# TIDA-00643_8305.net
KiCad netlist of a schematic drawn in Altium Designer
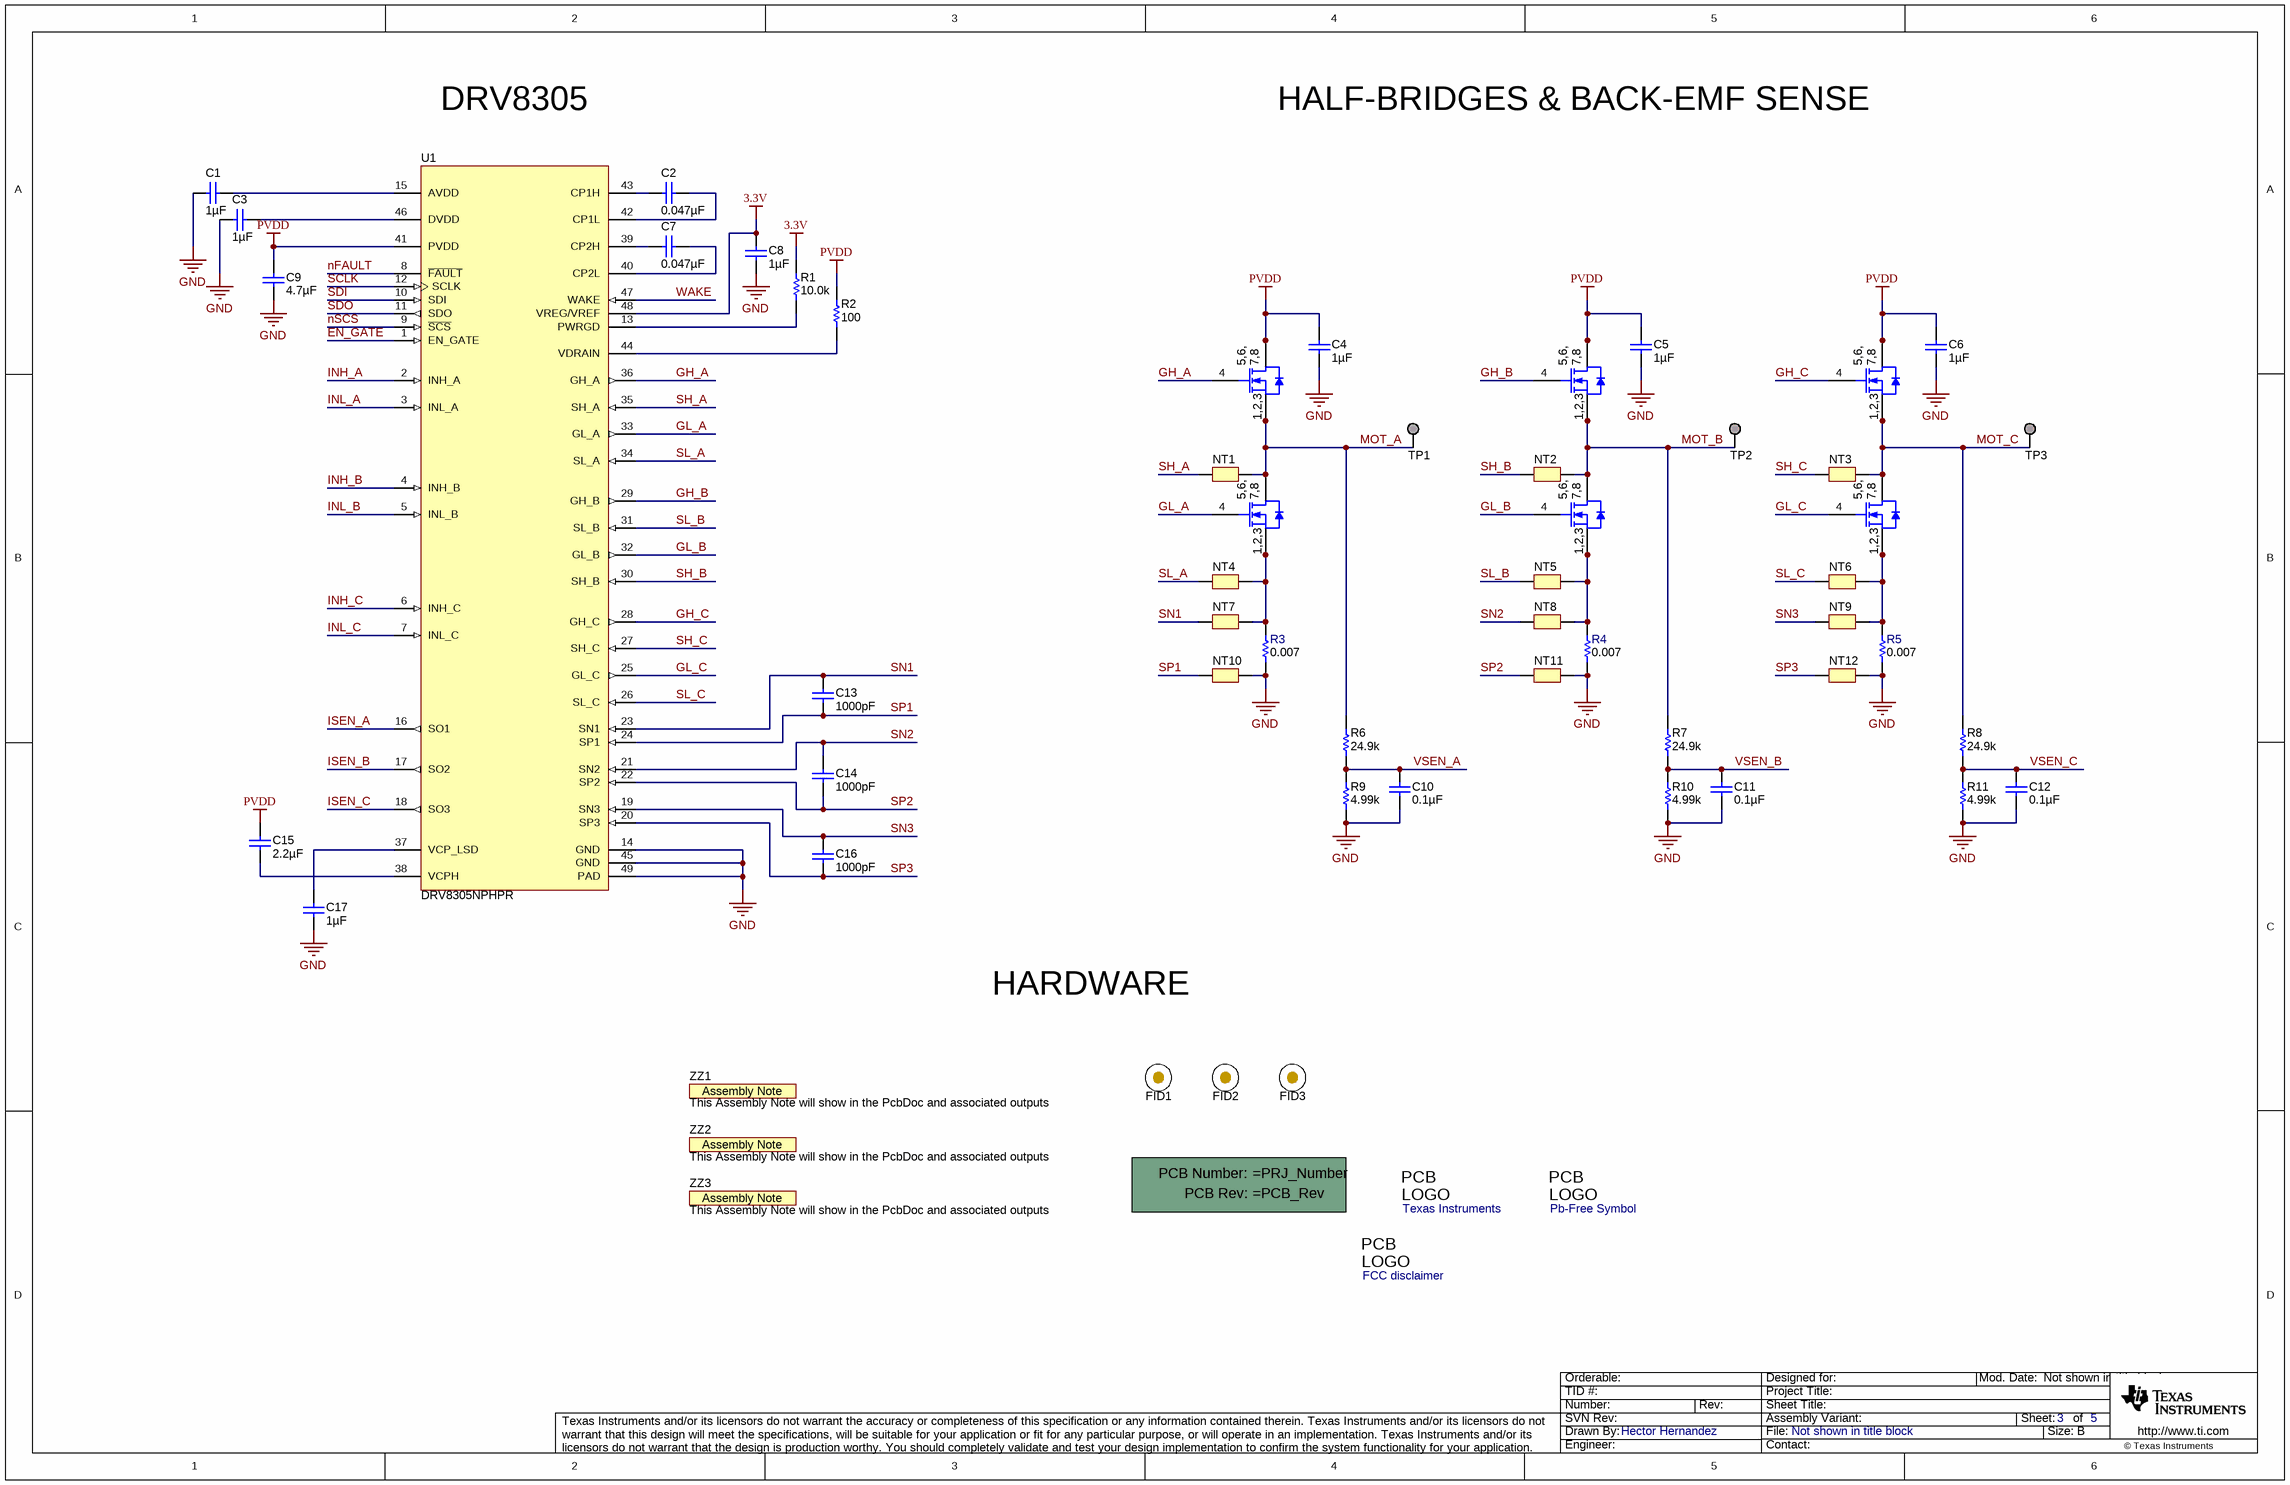
[diagram p0: TIDA-00643_8305.SchDoc]

(export (version "E")
  (design (tool "Eeschema 10.0.6"))
  (components
    (comp (ref "!PCB1")
      (value "Printed Circuit Board")
      (fields
        (field (name "MANUFACTURER") "Any")
        (field (name "SYMBOLCREATOR") "a0412235")
        (field (name "PUBLISHER") "Texas Instruments")
      )
      (libsource (lib "Hardware") (part "PCB"))
    )
    (comp (ref "C1")
      (value "GMK107BJ105KA-T")
      (footprint "0603L")
      (description "CAP, CERM, 1 µF, 35 V, +/- 10%, X5R, 0603")
      (fields
        (field (name "VALUEDISPLAYED") "1µF")
        (field (name "MANUFACTURER") "Taiyo Yuden")
        (field (name "PUBLISHER") "Texas Instruments")
      )
      (libsource (lib "Capacitor_Ceramic") (part "GMK107BJ105KA-T"))
    )
    (comp (ref "C2")
      (value "GRM188R71E473KA01D")
      (footprint "0603L")
      (description "CAP, CERM, 0.047 µF, 25 V, +/- 10%, X7R, 0603")
      (fields
        (field (name "VALUEDISPLAYED") "0.047µF")
        (field (name "MANUFACTURER") "MuRata")
        (field (name "PUBLISHER") "Texas Instruments")
      )
      (libsource (lib "Capacitor_Ceramic") (part "GRM188R71E473KA01D"))
    )
    (comp (ref "C3")
      (value "GMK107BJ105KA-T")
      (footprint "0603L")
      (description "CAP, CERM, 1 µF, 35 V, +/- 10%, X5R, 0603")
      (fields
        (field (name "VALUEDISPLAYED") "1µF")
        (field (name "MANUFACTURER") "Taiyo Yuden")
        (field (name "PUBLISHER") "Texas Instruments")
      )
      (libsource (lib "Capacitor_Ceramic") (part "GMK107BJ105KA-T"))
    )
    (comp (ref "C4")
      (value "GMK107BJ105KA-T")
      (footprint "0603L")
      (description "CAP, CERM, 1 µF, 35 V, +/- 10%, X5R, 0603")
      (fields
        (field (name "VALUEDISPLAYED") "1µF")
        (field (name "MANUFACTURER") "Taiyo Yuden")
        (field (name "PUBLISHER") "Texas Instruments")
      )
      (libsource (lib "Capacitor_Ceramic") (part "GMK107BJ105KA-T"))
    )
    (comp (ref "C5")
      (value "GMK107BJ105KA-T")
      (footprint "0603L")
      (description "CAP, CERM, 1 µF, 35 V, +/- 10%, X5R, 0603")
      (fields
        (field (name "VALUEDISPLAYED") "1µF")
        (field (name "MANUFACTURER") "Taiyo Yuden")
        (field (name "PUBLISHER") "Texas Instruments")
      )
      (libsource (lib "Capacitor_Ceramic") (part "GMK107BJ105KA-T"))
    )
    (comp (ref "C6")
      (value "GMK107BJ105KA-T")
      (footprint "0603L")
      (description "CAP, CERM, 1 µF, 35 V, +/- 10%, X5R, 0603")
      (fields
        (field (name "VALUEDISPLAYED") "1µF")
        (field (name "MANUFACTURER") "Taiyo Yuden")
        (field (name "PUBLISHER") "Texas Instruments")
      )
      (libsource (lib "Capacitor_Ceramic") (part "GMK107BJ105KA-T"))
    )
    (comp (ref "C7")
      (value "GRM188R71E473KA01D")
      (footprint "0603L")
      (description "CAP, CERM, 0.047 µF, 25 V, +/- 10%, X7R, 0603")
      (fields
        (field (name "VALUEDISPLAYED") "0.047µF")
        (field (name "MANUFACTURER") "MuRata")
        (field (name "PUBLISHER") "Texas Instruments")
      )
      (libsource (lib "Capacitor_Ceramic") (part "GRM188R71E473KA01D"))
    )
    (comp (ref "C8")
      (value "GRM188R61C105KA93D")
      (footprint "0603L")
      (description "CAP, CERM, 1 µF, 16 V, +/- 10%, X5R, 0603")
      (fields
        (field (name "VALUEDISPLAYED") "1µF")
        (field (name "MANUFACTURER") "MuRata")
        (field (name "PUBLISHER") "Texas Instruments")
      )
      (libsource (lib "Capacitor_Ceramic") (part "GRM188R61C105KA93D"))
    )
    (comp (ref "C9")
      (value "GRM188R6YA475KE15D")
      (footprint "0603_100L")
      (description "CAP, CERM, 4.7 µF, 35 V, +/- 10%, X5R, 0603")
      (fields
        (field (name "VALUEDISPLAYED") "4.7µF")
        (field (name "MANUFACTURER") "MuRata")
        (field (name "PUBLISHER") "Texas Instruments")
      )
      (libsource (lib "Capacitor_Ceramic") (part "GRM188R6YA475KE15D"))
    )
    (comp (ref "C10")
      (value "885012105016")
      (footprint "0402L")
      (description "CAP, CERM, 0.1 µF, 16 V, +/- 20%, X5R, 0402")
      (fields
        (field (name "VALUEDISPLAYED") "0.1µF")
        (field (name "MANUFACTURER") "Wurth Elektronik")
        (field (name "PUBLISHER") "Texas Instruments")
      )
      (libsource (lib "Capacitor_Ceramic") (part "885012105016"))
    )
    (comp (ref "C11")
      (value "885012105016")
      (footprint "0402L")
      (description "CAP, CERM, 0.1 µF, 16 V, +/- 20%, X5R, 0402")
      (fields
        (field (name "VALUEDISPLAYED") "0.1µF")
        (field (name "MANUFACTURER") "Wurth Elektronik")
        (field (name "PUBLISHER") "Texas Instruments")
      )
      (libsource (lib "Capacitor_Ceramic") (part "885012105016"))
    )
    (comp (ref "C12")
      (value "885012105016")
      (footprint "0402L")
      (description "CAP, CERM, 0.1 µF, 16 V, +/- 20%, X5R, 0402")
      (fields
        (field (name "VALUEDISPLAYED") "0.1µF")
        (field (name "MANUFACTURER") "Wurth Elektronik")
        (field (name "PUBLISHER") "Texas Instruments")
      )
      (libsource (lib "Capacitor_Ceramic") (part "885012105016"))
    )
    (comp (ref "C13")
      (value "GRM1555C1H102JA01D")
      (footprint "0402L")
      (description "CAP, CERM, 1000 pF, 50 V, +/- 5%, C0G/NP0, 0402")
      (fields
        (field (name "VALUEDISPLAYED") "1000pF")
        (field (name "MANUFACTURER") "MuRata")
        (field (name "PUBLISHER") "Texas Instruments")
      )
      (libsource (lib "Capacitor_Ceramic") (part "GRM1555C1H102JA01D"))
    )
    (comp (ref "C14")
      (value "GRM1555C1H102JA01D")
      (footprint "0402L")
      (description "CAP, CERM, 1000 pF, 50 V, +/- 5%, C0G/NP0, 0402")
      (fields
        (field (name "VALUEDISPLAYED") "1000pF")
        (field (name "MANUFACTURER") "MuRata")
        (field (name "PUBLISHER") "Texas Instruments")
      )
      (libsource (lib "Capacitor_Ceramic") (part "GRM1555C1H102JA01D"))
    )
    (comp (ref "C15")
      (value "GRM188R6YA225KA12D")
      (footprint "0603L")
      (description "CAP, CERM, 2.2 µF, 35 V, +/- 10%, X5R, 0603")
      (fields
        (field (name "VALUEDISPLAYED") "2.2µF")
        (field (name "MANUFACTURER") "MuRata")
        (field (name "PUBLISHER") "Texas Instruments")
      )
      (libsource (lib "Capacitor_Ceramic") (part "GRM188R6YA225KA12D"))
    )
    (comp (ref "C16")
      (value "GRM1555C1H102JA01D")
      (footprint "0402L")
      (description "CAP, CERM, 1000 pF, 50 V, +/- 5%, C0G/NP0, 0402")
      (fields
        (field (name "VALUEDISPLAYED") "1000pF")
        (field (name "MANUFACTURER") "MuRata")
        (field (name "PUBLISHER") "Texas Instruments")
      )
      (libsource (lib "Capacitor_Ceramic") (part "GRM1555C1H102JA01D"))
    )
    (comp (ref "C17")
      (value "GMK107BJ105KA-T")
      (footprint "0603L")
      (description "CAP, CERM, 1 µF, 35 V, +/- 10%, X5R, 0603")
      (fields
        (field (name "VALUEDISPLAYED") "1µF")
        (field (name "MANUFACTURER") "Taiyo Yuden")
        (field (name "PUBLISHER") "Texas Instruments")
      )
      (libsource (lib "Capacitor_Ceramic") (part "GMK107BJ105KA-T"))
    )
    (comp (ref "FID1")
      (value "Fiducial")
      (footprint "Fiducial6.4-20")
      (description "Fiducial mark.  There is nothing to buy or mount.")
      (fields (field (name "SYMBOLCREATOR") "codlsc") (field (name "PUBLISHER") "Texas Instruments"))
      (libsource (lib "MiscParts") (part "Fiducial"))
    )
    (comp (ref "FID2")
      (value "Fiducial")
      (footprint "Fiducial6.4-20")
      (description "Fiducial mark.  There is nothing to buy or mount.")
      (fields (field (name "SYMBOLCREATOR") "codlsc") (field (name "PUBLISHER") "Texas Instruments"))
      (libsource (lib "MiscParts") (part "Fiducial"))
    )
    (comp (ref "FID3")
      (value "Fiducial")
      (footprint "Fiducial6.4-20")
      (description "Fiducial mark.  There is nothing to buy or mount.")
      (fields (field (name "SYMBOLCREATOR") "codlsc") (field (name "PUBLISHER") "Texas Instruments"))
      (libsource (lib "MiscParts") (part "Fiducial"))
    )
    (comp (ref "Logo1")
      (value "Texas Instruments")
      (footprint "TI_Symbol_Overlay_Small")
      (description "Texas Instrument Corporate Signature")
      (fields (field (name "SYMBOLCREATOR") "a0412235") (field (name "PUBLISHER") "Texas Instruments"))
      (libsource (lib "Logos") (part "TI_Logo"))
    )
    (comp (ref "Logo2")
      (value "Pb-Free Symbol")
      (footprint "Pb-Free_Overlay_Small")
      (fields (field (name "SYMBOLCREATOR") "a0412235") (field (name "PUBLISHER") "Texas Instruments"))
      (libsource (lib "Logos") (part "Pb-Free"))
    )
    (comp (ref "Logo3")
      (value "FCC disclaimer")
      (footprint "FCC_disclaimer_stacked")
      (description "FCC_disclaimer")
      (fields (field (name "SYMBOLCREATOR") "codlsc") (field (name "PUBLISHER") "Texas Instruments"))
      (libsource (lib "Logos") (part "FCC_disclaimer"))
    )
    (comp (ref "NT1")
      (value "Net-Tie")
      (footprint "Net-Tie_10mil")
      (description "Single point connection between nets.")
      (fields (field (name "SYMBOLCREATOR") "codlsc") (field (name "PUBLISHER") "Texas Instruments"))
      (libsource (lib "MiscParts") (part "Net-Tie"))
    )
    (comp (ref "NT2")
      (value "Net-Tie")
      (footprint "Net-Tie_10mil")
      (description "Single point connection between nets.")
      (fields (field (name "SYMBOLCREATOR") "codlsc") (field (name "PUBLISHER") "Texas Instruments"))
      (libsource (lib "MiscParts") (part "Net-Tie"))
    )
    (comp (ref "NT3")
      (value "Net-Tie")
      (footprint "Net-Tie_10mil")
      (description "Single point connection between nets.")
      (fields (field (name "SYMBOLCREATOR") "codlsc") (field (name "PUBLISHER") "Texas Instruments"))
      (libsource (lib "MiscParts") (part "Net-Tie"))
    )
    (comp (ref "NT4")
      (value "Net-Tie")
      (footprint "Net-Tie_10mil")
      (description "Single point connection between nets.")
      (fields (field (name "SYMBOLCREATOR") "codlsc") (field (name "PUBLISHER") "Texas Instruments"))
      (libsource (lib "MiscParts") (part "Net-Tie"))
    )
    (comp (ref "NT5")
      (value "Net-Tie")
      (footprint "Net-Tie_10mil")
      (description "Single point connection between nets.")
      (fields (field (name "SYMBOLCREATOR") "codlsc") (field (name "PUBLISHER") "Texas Instruments"))
      (libsource (lib "MiscParts") (part "Net-Tie"))
    )
    (comp (ref "NT6")
      (value "Net-Tie")
      (footprint "Net-Tie_10mil")
      (description "Single point connection between nets.")
      (fields (field (name "SYMBOLCREATOR") "codlsc") (field (name "PUBLISHER") "Texas Instruments"))
      (libsource (lib "MiscParts") (part "Net-Tie"))
    )
    (comp (ref "NT7")
      (value "Net-Tie")
      (footprint "Net-Tie_10mil")
      (description "Single point connection between nets.")
      (fields (field (name "SYMBOLCREATOR") "codlsc") (field (name "PUBLISHER") "Texas Instruments"))
      (libsource (lib "MiscParts") (part "Net-Tie"))
    )
    (comp (ref "NT8")
      (value "Net-Tie")
      (footprint "Net-Tie_10mil")
      (description "Single point connection between nets.")
      (fields (field (name "SYMBOLCREATOR") "codlsc") (field (name "PUBLISHER") "Texas Instruments"))
      (libsource (lib "MiscParts") (part "Net-Tie"))
    )
    (comp (ref "NT9")
      (value "Net-Tie")
      (footprint "Net-Tie_10mil")
      (description "Single point connection between nets.")
      (fields (field (name "SYMBOLCREATOR") "codlsc") (field (name "PUBLISHER") "Texas Instruments"))
      (libsource (lib "MiscParts") (part "Net-Tie"))
    )
    (comp (ref "NT10")
      (value "Net-Tie")
      (footprint "Net-Tie_10mil")
      (description "Single point connection between nets.")
      (fields (field (name "SYMBOLCREATOR") "codlsc") (field (name "PUBLISHER") "Texas Instruments"))
      (libsource (lib "MiscParts") (part "Net-Tie"))
    )
    (comp (ref "NT11")
      (value "Net-Tie")
      (footprint "Net-Tie_10mil")
      (description "Single point connection between nets.")
      (fields (field (name "SYMBOLCREATOR") "codlsc") (field (name "PUBLISHER") "Texas Instruments"))
      (libsource (lib "MiscParts") (part "Net-Tie"))
    )
    (comp (ref "NT12")
      (value "Net-Tie")
      (footprint "Net-Tie_10mil")
      (description "Single point connection between nets.")
      (fields (field (name "SYMBOLCREATOR") "codlsc") (field (name "PUBLISHER") "Texas Instruments"))
      (libsource (lib "MiscParts") (part "Net-Tie"))
    )
    (comp (ref "Q1")
      (value "CSD17573Q5B")
      (footprint "TRANS_NexFET_Q5B")
      (description "MOSFET, N-CH, 30 V, 100 A, SON 5x6mm")
      (fields
        (field (name "MANUFACTURER") "Texas Instruments")
        (field (name "PUBLISHER") "Texas Instruments")
      )
      (libsource (lib "FETs") (part "CSD17573Q5B"))
    )
    (comp (ref "Q2")
      (value "CSD17573Q5B")
      (footprint "TRANS_NexFET_Q5B")
      (description "MOSFET, N-CH, 30 V, 100 A, SON 5x6mm")
      (fields
        (field (name "MANUFACTURER") "Texas Instruments")
        (field (name "PUBLISHER") "Texas Instruments")
      )
      (libsource (lib "FETs") (part "CSD17573Q5B"))
    )
    (comp (ref "Q3")
      (value "CSD17573Q5B")
      (footprint "TRANS_NexFET_Q5B")
      (description "MOSFET, N-CH, 30 V, 100 A, SON 5x6mm")
      (fields
        (field (name "MANUFACTURER") "Texas Instruments")
        (field (name "PUBLISHER") "Texas Instruments")
      )
      (libsource (lib "FETs") (part "CSD17573Q5B"))
    )
    (comp (ref "Q4")
      (value "CSD17573Q5B")
      (footprint "TRANS_NexFET_Q5B")
      (description "MOSFET, N-CH, 30 V, 100 A, SON 5x6mm")
      (fields
        (field (name "MANUFACTURER") "Texas Instruments")
        (field (name "PUBLISHER") "Texas Instruments")
      )
      (libsource (lib "FETs") (part "CSD17573Q5B"))
    )
    (comp (ref "Q5")
      (value "CSD17573Q5B")
      (footprint "TRANS_NexFET_Q5B")
      (description "MOSFET, N-CH, 30 V, 100 A, SON 5x6mm")
      (fields
        (field (name "MANUFACTURER") "Texas Instruments")
        (field (name "PUBLISHER") "Texas Instruments")
      )
      (libsource (lib "FETs") (part "CSD17573Q5B"))
    )
    (comp (ref "Q6")
      (value "CSD17573Q5B")
      (footprint "TRANS_NexFET_Q5B")
      (description "MOSFET, N-CH, 30 V, 100 A, SON 5x6mm")
      (fields
        (field (name "MANUFACTURER") "Texas Instruments")
        (field (name "PUBLISHER") "Texas Instruments")
      )
      (libsource (lib "FETs") (part "CSD17573Q5B"))
    )
    (comp (ref "R1")
      (value "RC0603FR-0710KL")
      (footprint "0603L")
      (description "RES, 10.0 k, 1%, 0.1 W, 0603")
      (fields
        (field (name "VALUEDISPLAYED") "10.0k")
        (field (name "MANUFACTURER") "Yageo America")
        (field (name "PUBLISHER") "Texas Instruments")
      )
      (libsource (lib "Resistor_0603") (part "RC0603FR-0710KL"))
    )
    (comp (ref "R2")
      (value "RC0603FR-07100RL")
      (footprint "0603L")
      (description "RES, 100, 1%, 0.1 W, 0603")
      (fields
        (field (name "VALUEDISPLAYED") "100")
        (field (name "MANUFACTURER") "Yageo America")
        (field (name "PUBLISHER") "Texas Instruments")
      )
      (libsource (lib "Resistor_0603") (part "RC0603FR-07100RL"))
    )
    (comp (ref "R3")
      (value "PMR100HZPFU7L00")
      (footprint "2512L")
      (description "RES, 0.007, 1%, 2 W, 2512")
      (fields
        (field (name "VALUEDISPLAYED") "0.007")
        (field (name "MANUFACTURER") "Rohm")
        (field (name "PUBLISHER") "Texas Instruments")
      )
      (libsource (lib "Resistor_2512") (part "PMR100HZPFU7L00"))
    )
    (comp (ref "R4")
      (value "PMR100HZPFU7L00")
      (footprint "2512L")
      (description "RES, 0.007, 1%, 2 W, 2512")
      (fields
        (field (name "VALUEDISPLAYED") "0.007")
        (field (name "MANUFACTURER") "Rohm")
        (field (name "PUBLISHER") "Texas Instruments")
      )
      (libsource (lib "Resistor_2512") (part "PMR100HZPFU7L00"))
    )
    (comp (ref "R5")
      (value "PMR100HZPFU7L00")
      (footprint "2512L")
      (description "RES, 0.007, 1%, 2 W, 2512")
      (fields
        (field (name "VALUEDISPLAYED") "0.007")
        (field (name "MANUFACTURER") "Rohm")
        (field (name "PUBLISHER") "Texas Instruments")
      )
      (libsource (lib "Resistor_2512") (part "PMR100HZPFU7L00"))
    )
    (comp (ref "R6")
      (value "CRCW060324K9FKEA")
      (footprint "0603L")
      (description "RES, 24.9 k, 1%, 0.1 W, 0603")
      (fields
        (field (name "VALUEDISPLAYED") "24.9k")
        (field (name "MANUFACTURER") "Vishay-Dale")
        (field (name "PUBLISHER") "Texas Instruments")
      )
      (libsource (lib "Resistor_0603") (part "CRCW060324K9FKEA"))
    )
    (comp (ref "R7")
      (value "CRCW060324K9FKEA")
      (footprint "0603L")
      (description "RES, 24.9 k, 1%, 0.1 W, 0603")
      (fields
        (field (name "VALUEDISPLAYED") "24.9k")
        (field (name "MANUFACTURER") "Vishay-Dale")
        (field (name "PUBLISHER") "Texas Instruments")
      )
      (libsource (lib "Resistor_0603") (part "CRCW060324K9FKEA"))
    )
    (comp (ref "R8")
      (value "CRCW060324K9FKEA")
      (footprint "0603L")
      (description "RES, 24.9 k, 1%, 0.1 W, 0603")
      (fields
        (field (name "VALUEDISPLAYED") "24.9k")
        (field (name "MANUFACTURER") "Vishay-Dale")
        (field (name "PUBLISHER") "Texas Instruments")
      )
      (libsource (lib "Resistor_0603") (part "CRCW060324K9FKEA"))
    )
    (comp (ref "R9")
      (value "CRCW04024K99FKED")
      (footprint "0402L")
      (description "RES, 4.99 k, 1%, 0.063 W, 0402")
      (fields
        (field (name "VALUEDISPLAYED") "4.99k")
        (field (name "MANUFACTURER") "Vishay-Dale")
        (field (name "PUBLISHER") "Texas Instruments")
      )
      (libsource (lib "Resistor_0402") (part "CRCW04024K99FKED"))
    )
    (comp (ref "R10")
      (value "CRCW04024K99FKED")
      (footprint "0402L")
      (description "RES, 4.99 k, 1%, 0.063 W, 0402")
      (fields
        (field (name "VALUEDISPLAYED") "4.99k")
        (field (name "MANUFACTURER") "Vishay-Dale")
        (field (name "PUBLISHER") "Texas Instruments")
      )
      (libsource (lib "Resistor_0402") (part "CRCW04024K99FKED"))
    )
    (comp (ref "R11")
      (value "CRCW04024K99FKED")
      (footprint "0402L")
      (description "RES, 4.99 k, 1%, 0.063 W, 0402")
      (fields
        (field (name "VALUEDISPLAYED") "4.99k")
        (field (name "MANUFACTURER") "Vishay-Dale")
        (field (name "PUBLISHER") "Texas Instruments")
      )
      (libsource (lib "Resistor_0402") (part "CRCW04024K99FKED"))
    )
    (comp (ref "TP1")
      (value "TESTPOINT")
      (footprint "TESTPOINT")
      (description "TEST POINT.  No entry in BOM.")
      (fields (field (name "PUBLISHER") "Texas Instruments"))
      (libsource (lib "MiscParts") (part "TESTPOINT"))
    )
    (comp (ref "TP2")
      (value "TESTPOINT")
      (footprint "TESTPOINT")
      (description "TEST POINT.  No entry in BOM.")
      (fields (field (name "PUBLISHER") "Texas Instruments"))
      (libsource (lib "MiscParts") (part "TESTPOINT"))
    )
    (comp (ref "TP3")
      (value "TESTPOINT")
      (footprint "TESTPOINT")
      (description "TEST POINT.  No entry in BOM.")
      (fields (field (name "PUBLISHER") "Texas Instruments"))
      (libsource (lib "MiscParts") (part "TESTPOINT"))
    )
    (comp (ref "U1")
      (value "DRV8305NPHPR")
      (footprint "PHP0048G_L")
      (fields
        (field (name "ALTERNATE PARTNUMBER") "DRV8305NPHP")
        (field (name "MANUFACTURER") "Texas Instruments")
        (field (name "SYMBOLCREATOR") "Altium")
        (field (name "PUBLISHER") "Texas Instruments")
      )
      (libsource (lib "TI_Pre_RTM") (part "DRV83053EPHPRQ1"))
    )
    (comp (ref "ZZ1")
      (value "This Assembly Note will show in the PcbDoc and associated outputs")
      (footprint "AssemblyNote")
      (fields (field (name "SYMBOLCREATOR") "codlsc") (field (name "PUBLISHER") "Texas Instruments"))
      (libsource (lib "Hardware") (part "AssemblyNote"))
    )
    (comp (ref "ZZ2")
      (value "This Assembly Note will show in the PcbDoc and associated outputs")
      (footprint "AssemblyNote")
      (fields (field (name "SYMBOLCREATOR") "codlsc") (field (name "PUBLISHER") "Texas Instruments"))
      (libsource (lib "Hardware") (part "AssemblyNote"))
    )
    (comp (ref "ZZ3")
      (value "This Assembly Note will show in the PcbDoc and associated outputs")
      (footprint "AssemblyNote")
      (fields (field (name "SYMBOLCREATOR") "codlsc") (field (name "PUBLISHER") "Texas Instruments"))
      (libsource (lib "Hardware") (part "AssemblyNote"))
    )
  )
  (nets
    (net (code "1") (name "/EN_GATE") (class "Default")
      (node (ref "U1") (pin "1") (pinfunction "EN_GATE_1") (pintype "input"))
    )
    (net (code "2") (name "/GH_A") (class "Default")
      (node (ref "Q1") (pin "4") (pinfunction "G_4") (pintype "passive"))
      (node (ref "U1") (pin "36") (pinfunction "GH_A_36") (pintype "output"))
    )
    (net (code "3") (name "/GH_B") (class "Default")
      (node (ref "Q2") (pin "4") (pinfunction "G_4") (pintype "passive"))
      (node (ref "U1") (pin "29") (pinfunction "GH_B_29") (pintype "output"))
    )
    (net (code "4") (name "/GH_C") (class "Default")
      (node (ref "Q3") (pin "4") (pinfunction "G_4") (pintype "passive"))
      (node (ref "U1") (pin "28") (pinfunction "GH_C_28") (pintype "output"))
    )
    (net (code "5") (name "/GL_A") (class "Default")
      (node (ref "Q4") (pin "4") (pinfunction "G_4") (pintype "passive"))
      (node (ref "U1") (pin "33") (pinfunction "GL_A_33") (pintype "output"))
    )
    (net (code "6") (name "/GL_B") (class "Default")
      (node (ref "Q5") (pin "4") (pinfunction "G_4") (pintype "passive"))
      (node (ref "U1") (pin "32") (pinfunction "GL_B_32") (pintype "output"))
    )
    (net (code "7") (name "/GL_C") (class "Default")
      (node (ref "Q6") (pin "4") (pinfunction "G_4") (pintype "passive"))
      (node (ref "U1") (pin "25") (pinfunction "GL_C_25") (pintype "output"))
    )
    (net (code "8") (name "/INH_A") (class "Default")
      (node (ref "U1") (pin "2") (pinfunction "INH_A_2") (pintype "input"))
    )
    (net (code "9") (name "/INH_B") (class "Default")
      (node (ref "U1") (pin "4") (pinfunction "INH_B_4") (pintype "input"))
    )
    (net (code "10") (name "/INH_C") (class "Default")
      (node (ref "U1") (pin "6") (pinfunction "INH_C_6") (pintype "input"))
    )
    (net (code "11") (name "/INL_A") (class "Default")
      (node (ref "U1") (pin "3") (pinfunction "INL_A_3") (pintype "input"))
    )
    (net (code "12") (name "/INL_B") (class "Default")
      (node (ref "U1") (pin "5") (pinfunction "INL_B_5") (pintype "input"))
    )
    (net (code "13") (name "/INL_C") (class "Default")
      (node (ref "U1") (pin "7") (pinfunction "INL_C_7") (pintype "input"))
    )
    (net (code "14") (name "/ISEN_A") (class "Default")
      (node (ref "U1") (pin "16") (pinfunction "SO1_16") (pintype "output"))
    )
    (net (code "15") (name "/ISEN_B") (class "Default")
      (node (ref "U1") (pin "17") (pinfunction "SO2_17") (pintype "output"))
    )
    (net (code "16") (name "/ISEN_C") (class "Default")
      (node (ref "U1") (pin "18") (pinfunction "SO3_18") (pintype "output"))
    )
    (net (code "17") (name "/MOT_A") (class "Default")
      (node (ref "NT1") (pin "2") (pinfunction "2_2") (pintype "passive"))
      (node (ref "Q1") (pin "1") (pinfunction "S_1") (pintype "passive"))
      (node (ref "Q1") (pin "2") (pinfunction "S_2") (pintype "passive"))
      (node (ref "Q1") (pin "3") (pinfunction "S_3") (pintype "passive"))
      (node (ref "Q4") (pin "5") (pinfunction "D_5") (pintype "passive"))
      (node (ref "Q4") (pin "6") (pinfunction "D_6") (pintype "passive"))
      (node (ref "Q4") (pin "7") (pinfunction "D_7") (pintype "passive"))
      (node (ref "Q4") (pin "8") (pinfunction "D_8") (pintype "passive"))
      (node (ref "R6") (pin "2") (pinfunction "2_2") (pintype "passive"))
      (node (ref "TP1") (pin "1") (pintype "passive"))
    )
    (net (code "18") (name "/MOT_B") (class "Default")
      (node (ref "NT2") (pin "2") (pinfunction "2_2") (pintype "passive"))
      (node (ref "Q2") (pin "1") (pinfunction "S_1") (pintype "passive"))
      (node (ref "Q2") (pin "2") (pinfunction "S_2") (pintype "passive"))
      (node (ref "Q2") (pin "3") (pinfunction "S_3") (pintype "passive"))
      (node (ref "Q5") (pin "5") (pinfunction "D_5") (pintype "passive"))
      (node (ref "Q5") (pin "6") (pinfunction "D_6") (pintype "passive"))
      (node (ref "Q5") (pin "7") (pinfunction "D_7") (pintype "passive"))
      (node (ref "Q5") (pin "8") (pinfunction "D_8") (pintype "passive"))
      (node (ref "R7") (pin "2") (pinfunction "2_2") (pintype "passive"))
      (node (ref "TP2") (pin "1") (pintype "passive"))
    )
    (net (code "19") (name "/MOT_C") (class "Default")
      (node (ref "NT3") (pin "2") (pinfunction "2_2") (pintype "passive"))
      (node (ref "Q3") (pin "1") (pinfunction "S_1") (pintype "passive"))
      (node (ref "Q3") (pin "2") (pinfunction "S_2") (pintype "passive"))
      (node (ref "Q3") (pin "3") (pinfunction "S_3") (pintype "passive"))
      (node (ref "Q6") (pin "5") (pinfunction "D_5") (pintype "passive"))
      (node (ref "Q6") (pin "6") (pinfunction "D_6") (pintype "passive"))
      (node (ref "Q6") (pin "7") (pinfunction "D_7") (pintype "passive"))
      (node (ref "Q6") (pin "8") (pinfunction "D_8") (pintype "passive"))
      (node (ref "R8") (pin "2") (pinfunction "2_2") (pintype "passive"))
      (node (ref "TP3") (pin "1") (pintype "passive"))
    )
    (net (code "20") (name "/SCLK") (class "Default")
      (node (ref "U1") (pin "12") (pinfunction "SCLK_12") (pintype "input"))
    )
    (net (code "21") (name "/SDI") (class "Default")
      (node (ref "U1") (pin "10") (pinfunction "SDI_10") (pintype "input"))
    )
    (net (code "22") (name "/SDO") (class "Default")
      (node (ref "U1") (pin "11") (pinfunction "SDO_11") (pintype "output"))
    )
    (net (code "23") (name "/SH_A") (class "Default")
      (node (ref "NT1") (pin "1") (pinfunction "1_1") (pintype "passive"))
      (node (ref "U1") (pin "35") (pinfunction "SH_A_35") (pintype "input"))
    )
    (net (code "24") (name "/SH_B") (class "Default")
      (node (ref "NT2") (pin "1") (pinfunction "1_1") (pintype "passive"))
      (node (ref "U1") (pin "30") (pinfunction "SH_B_30") (pintype "input"))
    )
    (net (code "25") (name "/SH_C") (class "Default")
      (node (ref "NT3") (pin "1") (pinfunction "1_1") (pintype "passive"))
      (node (ref "U1") (pin "27") (pinfunction "SH_C_27") (pintype "input"))
    )
    (net (code "26") (name "/SL_A") (class "Default")
      (node (ref "NT4") (pin "1") (pinfunction "1_1") (pintype "passive"))
      (node (ref "U1") (pin "34") (pinfunction "SL_A_34") (pintype "input"))
    )
    (net (code "27") (name "/SL_B") (class "Default")
      (node (ref "NT5") (pin "1") (pinfunction "1_1") (pintype "passive"))
      (node (ref "U1") (pin "31") (pinfunction "SL_B_31") (pintype "input"))
    )
    (net (code "28") (name "/SL_C") (class "Default")
      (node (ref "NT6") (pin "1") (pinfunction "1_1") (pintype "passive"))
      (node (ref "U1") (pin "26") (pinfunction "SL_C_26") (pintype "input"))
    )
    (net (code "29") (name "/SN1") (class "Default")
      (node (ref "C13") (pin "1") (pinfunction "1_1") (pintype "passive"))
      (node (ref "NT7") (pin "1") (pinfunction "1_1") (pintype "passive"))
      (node (ref "U1") (pin "23") (pinfunction "SN1_23") (pintype "input"))
    )
    (net (code "30") (name "/SN2") (class "Default")
      (node (ref "C14") (pin "1") (pinfunction "1_1") (pintype "passive"))
      (node (ref "NT8") (pin "1") (pinfunction "1_1") (pintype "passive"))
      (node (ref "U1") (pin "21") (pinfunction "SN2_21") (pintype "input"))
    )
    (net (code "31") (name "/SN3") (class "Default")
      (node (ref "C16") (pin "1") (pinfunction "1_1") (pintype "passive"))
      (node (ref "NT9") (pin "1") (pinfunction "1_1") (pintype "passive"))
      (node (ref "U1") (pin "19") (pinfunction "SN3_19") (pintype "input"))
    )
    (net (code "32") (name "/SP1") (class "Default")
      (node (ref "C13") (pin "2") (pinfunction "2_2") (pintype "passive"))
      (node (ref "NT10") (pin "1") (pinfunction "1_1") (pintype "passive"))
      (node (ref "U1") (pin "24") (pinfunction "SP1_24") (pintype "input"))
    )
    (net (code "33") (name "/SP2") (class "Default")
      (node (ref "C14") (pin "2") (pinfunction "2_2") (pintype "passive"))
      (node (ref "NT11") (pin "1") (pinfunction "1_1") (pintype "passive"))
      (node (ref "U1") (pin "22") (pinfunction "SP2_22") (pintype "input"))
    )
    (net (code "34") (name "/SP3") (class "Default")
      (node (ref "C16") (pin "2") (pinfunction "2_2") (pintype "passive"))
      (node (ref "NT12") (pin "1") (pinfunction "1_1") (pintype "passive"))
      (node (ref "U1") (pin "20") (pinfunction "SP3_20") (pintype "input"))
    )
    (net (code "35") (name "/VSEN_A") (class "Default")
      (node (ref "C10") (pin "1") (pinfunction "1_1") (pintype "passive"))
      (node (ref "R6") (pin "1") (pinfunction "1_1") (pintype "passive"))
      (node (ref "R9") (pin "2") (pinfunction "2_2") (pintype "passive"))
    )
    (net (code "36") (name "/VSEN_B") (class "Default")
      (node (ref "C11") (pin "1") (pinfunction "1_1") (pintype "passive"))
      (node (ref "R10") (pin "2") (pinfunction "2_2") (pintype "passive"))
      (node (ref "R7") (pin "1") (pinfunction "1_1") (pintype "passive"))
    )
    (net (code "37") (name "/VSEN_C") (class "Default")
      (node (ref "C12") (pin "1") (pinfunction "1_1") (pintype "passive"))
      (node (ref "R11") (pin "2") (pinfunction "2_2") (pintype "passive"))
      (node (ref "R8") (pin "1") (pinfunction "1_1") (pintype "passive"))
    )
    (net (code "38") (name "/WAKE") (class "Default")
      (node (ref "U1") (pin "47") (pinfunction "WAKE_47") (pintype "input"))
    )
    (net (code "39") (name "/nFAULT") (class "Default")
      (node (ref "U1") (pin "8") (pinfunction "FAULT_8") (pintype "open_collector"))
    )
    (net (code "40") (name "/nSCS") (class "Default")
      (node (ref "U1") (pin "9") (pinfunction "SCS_9") (pintype "input"))
    )
    (net (code "41") (name "3.3V") (class "Default")
      (node (ref "C8") (pin "1") (pinfunction "1_1") (pintype "passive"))
      (node (ref "R1") (pin "2") (pinfunction "2_2") (pintype "passive"))
      (node (ref "U1") (pin "48") (pinfunction "VREG/VREF_48") (pintype "power_in"))
    )
    (net (code "42") (name "GND") (class "Default")
      (node (ref "C1") (pin "1") (pinfunction "1_1") (pintype "passive"))
      (node (ref "C10") (pin "2") (pinfunction "2_2") (pintype "passive"))
      (node (ref "C11") (pin "2") (pinfunction "2_2") (pintype "passive"))
      (node (ref "C12") (pin "2") (pinfunction "2_2") (pintype "passive"))
      (node (ref "C17") (pin "1") (pinfunction "1_1") (pintype "passive"))
      (node (ref "C3") (pin "1") (pinfunction "1_1") (pintype "passive"))
      (node (ref "C4") (pin "2") (pinfunction "2_2") (pintype "passive"))
      (node (ref "C5") (pin "2") (pinfunction "2_2") (pintype "passive"))
      (node (ref "C6") (pin "2") (pinfunction "2_2") (pintype "passive"))
      (node (ref "C8") (pin "2") (pinfunction "2_2") (pintype "passive"))
      (node (ref "C9") (pin "2") (pinfunction "2_2") (pintype "passive"))
      (node (ref "NT10") (pin "2") (pinfunction "2_2") (pintype "passive"))
      (node (ref "NT11") (pin "2") (pinfunction "2_2") (pintype "passive"))
      (node (ref "NT12") (pin "2") (pinfunction "2_2") (pintype "passive"))
      (node (ref "R10") (pin "1") (pinfunction "1_1") (pintype "passive"))
      (node (ref "R11") (pin "1") (pinfunction "1_1") (pintype "passive"))
      (node (ref "R3") (pin "1") (pinfunction "1_1") (pintype "passive"))
      (node (ref "R4") (pin "1") (pinfunction "1_1") (pintype "passive"))
      (node (ref "R5") (pin "1") (pinfunction "1_1") (pintype "passive"))
      (node (ref "R9") (pin "1") (pinfunction "1_1") (pintype "passive"))
      (node (ref "U1") (pin "14") (pinfunction "GND_14") (pintype "power_in"))
      (node (ref "U1") (pin "45") (pinfunction "GND_45") (pintype "power_in"))
      (node (ref "U1") (pin "49") (pinfunction "PAD_49") (pintype "power_in"))
    )
    (net (code "43") (name "Net-(NT4-Pad2)") (class "Default")
      (node (ref "NT4") (pin "2") (pinfunction "2_2") (pintype "passive"))
      (node (ref "NT7") (pin "2") (pinfunction "2_2") (pintype "passive"))
      (node (ref "Q4") (pin "1") (pinfunction "S_1") (pintype "passive"))
      (node (ref "Q4") (pin "2") (pinfunction "S_2") (pintype "passive"))
      (node (ref "Q4") (pin "3") (pinfunction "S_3") (pintype "passive"))
      (node (ref "R3") (pin "2") (pinfunction "2_2") (pintype "passive"))
    )
    (net (code "44") (name "Net-(NT5-Pad2)") (class "Default")
      (node (ref "NT5") (pin "2") (pinfunction "2_2") (pintype "passive"))
      (node (ref "NT8") (pin "2") (pinfunction "2_2") (pintype "passive"))
      (node (ref "Q5") (pin "1") (pinfunction "S_1") (pintype "passive"))
      (node (ref "Q5") (pin "2") (pinfunction "S_2") (pintype "passive"))
      (node (ref "Q5") (pin "3") (pinfunction "S_3") (pintype "passive"))
      (node (ref "R4") (pin "2") (pinfunction "2_2") (pintype "passive"))
    )
    (net (code "45") (name "Net-(NT6-Pad2)") (class "Default")
      (node (ref "NT6") (pin "2") (pinfunction "2_2") (pintype "passive"))
      (node (ref "NT9") (pin "2") (pinfunction "2_2") (pintype "passive"))
      (node (ref "Q6") (pin "1") (pinfunction "S_1") (pintype "passive"))
      (node (ref "Q6") (pin "2") (pinfunction "S_2") (pintype "passive"))
      (node (ref "Q6") (pin "3") (pinfunction "S_3") (pintype "passive"))
      (node (ref "R5") (pin "2") (pinfunction "2_2") (pintype "passive"))
    )
    (net (code "46") (name "Net-(U1-AVDD)") (class "Default")
      (node (ref "C1") (pin "2") (pinfunction "2_2") (pintype "passive"))
      (node (ref "U1") (pin "15") (pinfunction "AVDD_15") (pintype "power_in"))
    )
    (net (code "47") (name "Net-(U1-CP1H)") (class "Default")
      (node (ref "C2") (pin "2") (pinfunction "2_2") (pintype "passive"))
      (node (ref "U1") (pin "43") (pinfunction "CP1H_43") (pintype "passive"))
    )
    (net (code "48") (name "Net-(U1-CP1L)") (class "Default")
      (node (ref "C2") (pin "1") (pinfunction "1_1") (pintype "passive"))
      (node (ref "U1") (pin "42") (pinfunction "CP1L_42") (pintype "passive"))
    )
    (net (code "49") (name "Net-(U1-CP2H)") (class "Default")
      (node (ref "C7") (pin "2") (pinfunction "2_2") (pintype "passive"))
      (node (ref "U1") (pin "39") (pinfunction "CP2H_39") (pintype "passive"))
    )
    (net (code "50") (name "Net-(U1-CP2L)") (class "Default")
      (node (ref "C7") (pin "1") (pinfunction "1_1") (pintype "passive"))
      (node (ref "U1") (pin "40") (pinfunction "CP2L_40") (pintype "passive"))
    )
    (net (code "51") (name "Net-(U1-DVDD)") (class "Default")
      (node (ref "C3") (pin "2") (pinfunction "2_2") (pintype "passive"))
      (node (ref "U1") (pin "46") (pinfunction "DVDD_46") (pintype "power_in"))
    )
    (net (code "52") (name "Net-(U1-PWRGD)") (class "Default")
      (node (ref "R1") (pin "1") (pinfunction "1_1") (pintype "passive"))
      (node (ref "U1") (pin "13") (pinfunction "PWRGD_13") (pintype "open_collector"))
    )
    (net (code "53") (name "Net-(U1-VCPH)") (class "Default")
      (node (ref "C15") (pin "2") (pinfunction "2_2") (pintype "passive"))
      (node (ref "U1") (pin "38") (pinfunction "VCPH_38") (pintype "passive"))
    )
    (net (code "54") (name "Net-(U1-VCP_LSD)") (class "Default")
      (node (ref "C17") (pin "2") (pinfunction "2_2") (pintype "passive"))
      (node (ref "U1") (pin "37") (pinfunction "VCP_LSD_37") (pintype "passive"))
    )
    (net (code "55") (name "Net-(U1-VDRAIN)") (class "Default")
      (node (ref "R2") (pin "1") (pinfunction "1_1") (pintype "passive"))
      (node (ref "U1") (pin "44") (pinfunction "VDRAIN_44") (pintype "power_in"))
    )
    (net (code "56") (name "PVDD") (class "Default")
      (node (ref "C15") (pin "1") (pinfunction "1_1") (pintype "passive"))
      (node (ref "C4") (pin "1") (pinfunction "1_1") (pintype "passive"))
      (node (ref "C5") (pin "1") (pinfunction "1_1") (pintype "passive"))
      (node (ref "C6") (pin "1") (pinfunction "1_1") (pintype "passive"))
      (node (ref "C9") (pin "1") (pinfunction "1_1") (pintype "passive"))
      (node (ref "Q1") (pin "5") (pinfunction "D_5") (pintype "passive"))
      (node (ref "Q1") (pin "6") (pinfunction "D_6") (pintype "passive"))
      (node (ref "Q1") (pin "7") (pinfunction "D_7") (pintype "passive"))
      (node (ref "Q1") (pin "8") (pinfunction "D_8") (pintype "passive"))
      (node (ref "Q2") (pin "5") (pinfunction "D_5") (pintype "passive"))
      (node (ref "Q2") (pin "6") (pinfunction "D_6") (pintype "passive"))
      (node (ref "Q2") (pin "7") (pinfunction "D_7") (pintype "passive"))
      (node (ref "Q2") (pin "8") (pinfunction "D_8") (pintype "passive"))
      (node (ref "Q3") (pin "5") (pinfunction "D_5") (pintype "passive"))
      (node (ref "Q3") (pin "6") (pinfunction "D_6") (pintype "passive"))
      (node (ref "Q3") (pin "7") (pinfunction "D_7") (pintype "passive"))
      (node (ref "Q3") (pin "8") (pinfunction "D_8") (pintype "passive"))
      (node (ref "R2") (pin "2") (pinfunction "2_2") (pintype "passive"))
      (node (ref "U1") (pin "41") (pinfunction "PVDD_41") (pintype "power_in"))
    )
  )
)
